# diplexer-GPS-RF360-B8666.net
KiCad netlist of a schematic drawn in EAGLE
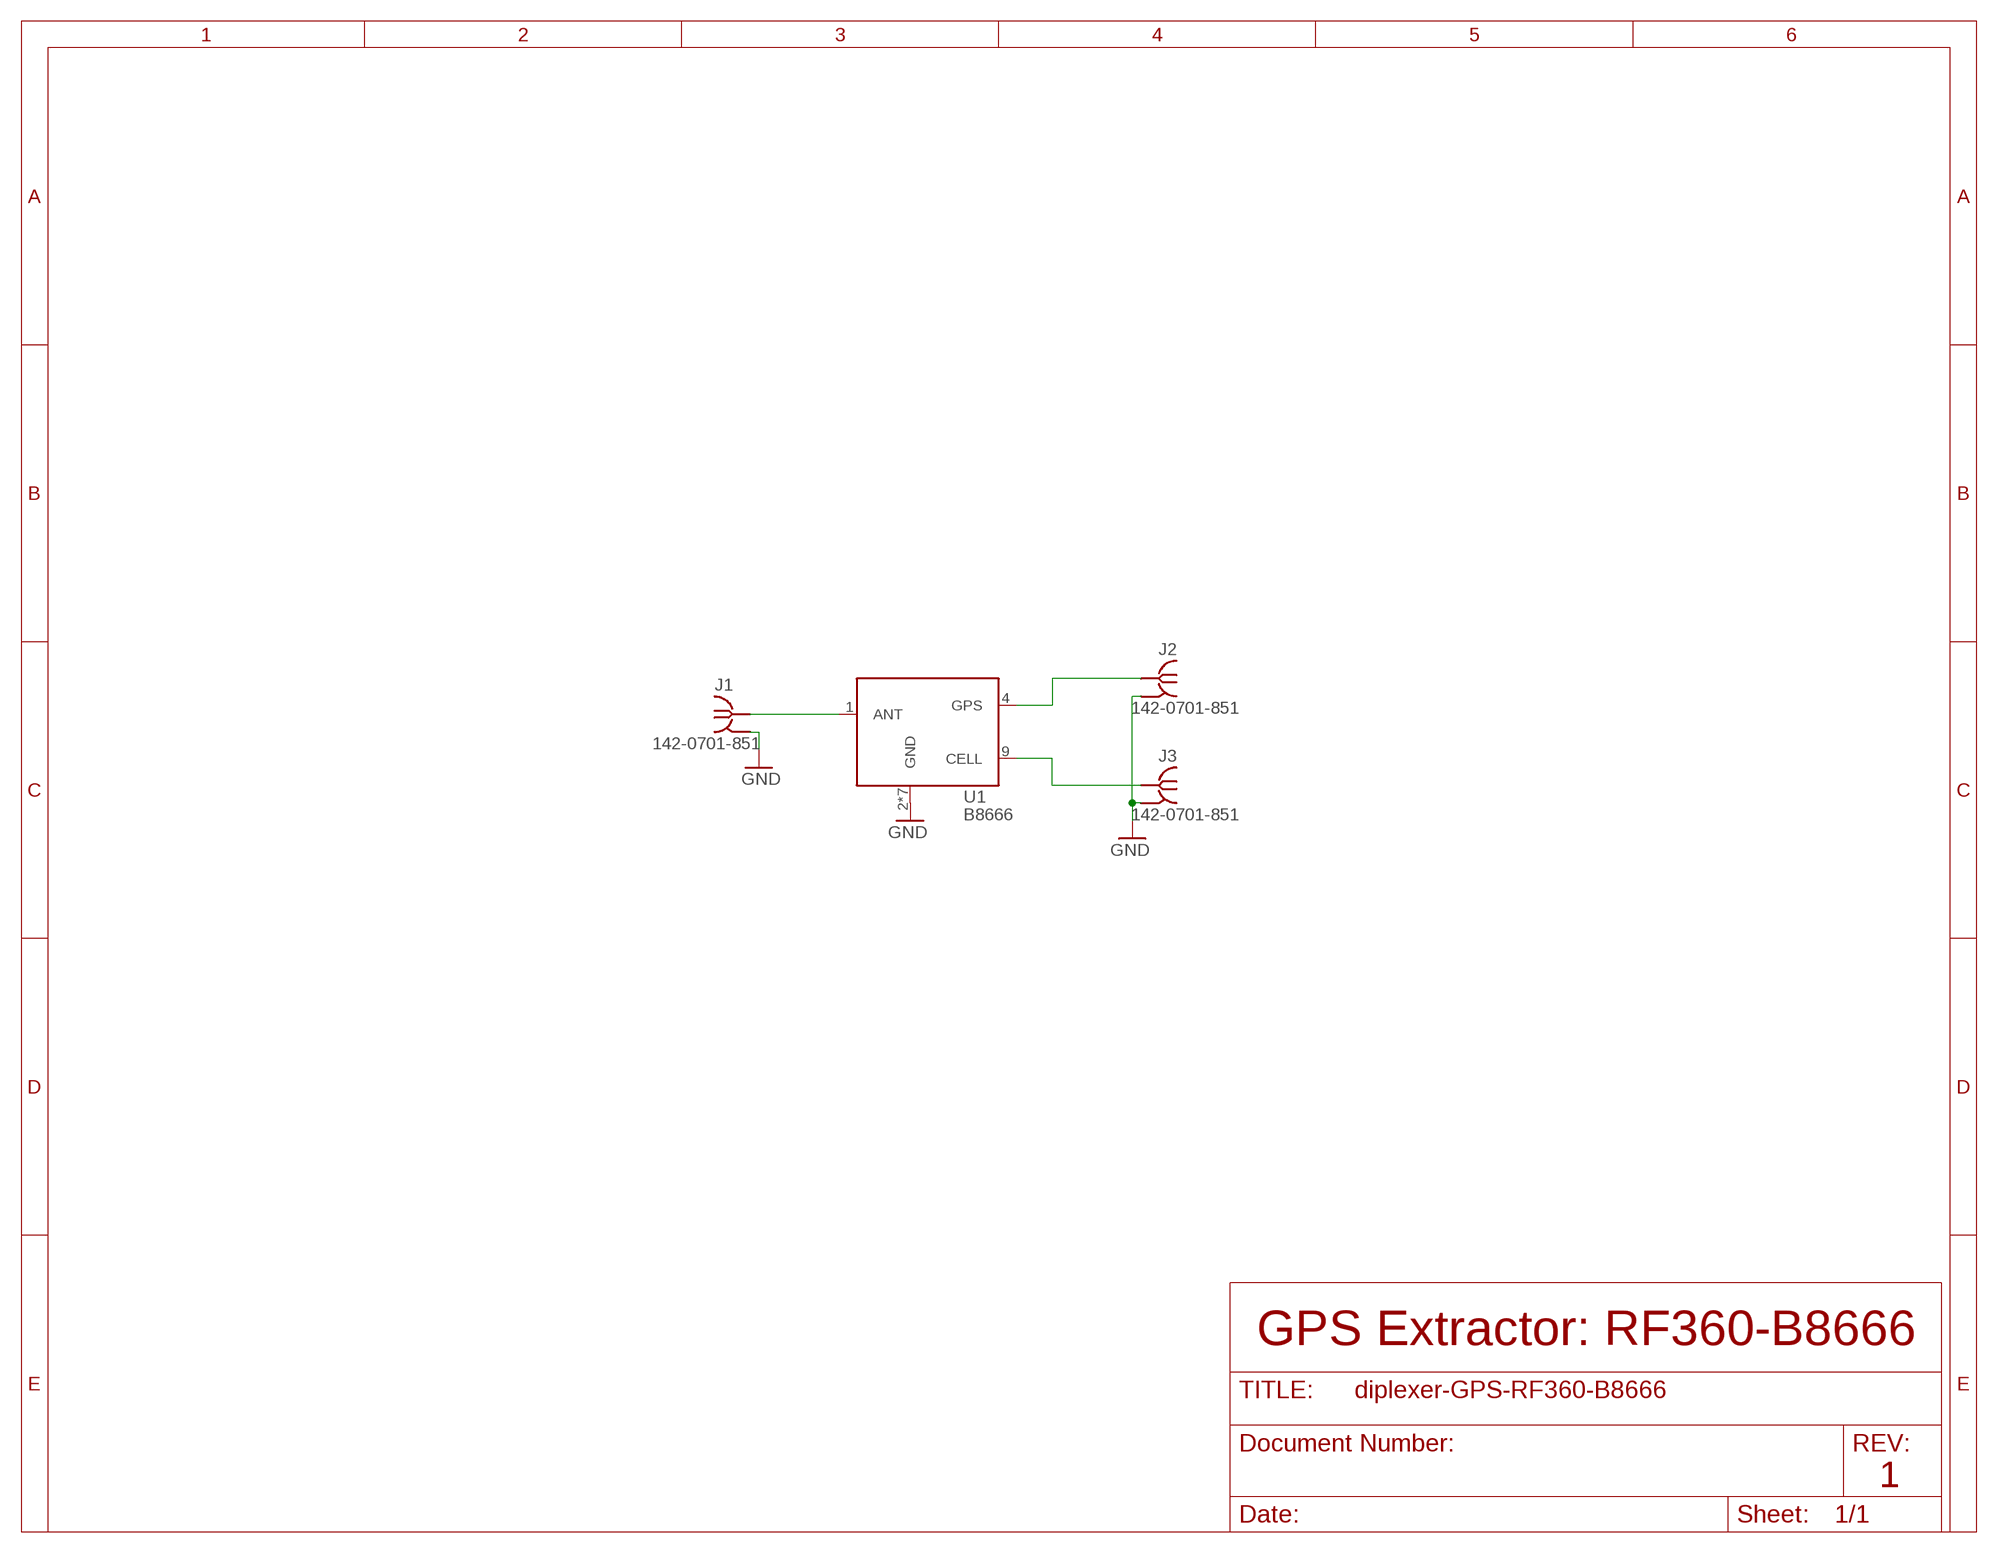
[diagram p0: schematic, sheet 1]

(export (version "E")
  (design (tool "Eeschema 10.0.6"))
  (components
    (comp (ref "J1")
      (value "142-0701-851")
      (footprint "eagle-import:142-0701-851")
      (libsource (lib "eagle-import") (part "142-0701-851"))
    )
    (comp (ref "J2")
      (value "142-0701-851")
      (footprint "eagle-import:142-0701-851")
      (libsource (lib "eagle-import") (part "142-0701-851"))
    )
    (comp (ref "J3")
      (value "142-0701-851")
      (footprint "eagle-import:142-0701-851")
      (libsource (lib "eagle-import") (part "142-0701-851"))
    )
    (comp (ref "U1")
      (value "B8666")
      (footprint "eagle-import:1.7X1.3")
      (libsource (lib "eagle-import") (part "B8666"))
    )
  )
  (nets
    (net (code "1") (name "GND") (class "Default")
      (node (ref "J1") (pin "GND1") (pinfunction "GND_GND1") (pintype "bidirectional"))
      (node (ref "J1") (pin "GND2") (pinfunction "GND_GND2") (pintype "bidirectional"))
      (node (ref "J1") (pin "GND3") (pinfunction "GND_GND3") (pintype "bidirectional"))
      (node (ref "J1") (pin "GND4") (pinfunction "GND_GND4") (pintype "bidirectional"))
      (node (ref "J2") (pin "GND1") (pinfunction "GND_GND1") (pintype "bidirectional"))
      (node (ref "J2") (pin "GND2") (pinfunction "GND_GND2") (pintype "bidirectional"))
      (node (ref "J2") (pin "GND3") (pinfunction "GND_GND3") (pintype "bidirectional"))
      (node (ref "J2") (pin "GND4") (pinfunction "GND_GND4") (pintype "bidirectional"))
      (node (ref "J3") (pin "GND1") (pinfunction "GND_GND1") (pintype "bidirectional"))
      (node (ref "J3") (pin "GND2") (pinfunction "GND_GND2") (pintype "bidirectional"))
      (node (ref "J3") (pin "GND3") (pinfunction "GND_GND3") (pintype "bidirectional"))
      (node (ref "J3") (pin "GND4") (pinfunction "GND_GND4") (pintype "bidirectional"))
      (node (ref "U1") (pin "10") (pinfunction "GND_10") (pintype "power_in"))
      (node (ref "U1") (pin "2") (pinfunction "GND_2") (pintype "power_in"))
      (node (ref "U1") (pin "3") (pinfunction "GND_3") (pintype "power_in"))
      (node (ref "U1") (pin "5") (pinfunction "GND_5") (pintype "power_in"))
      (node (ref "U1") (pin "6") (pinfunction "GND_6") (pintype "power_in"))
      (node (ref "U1") (pin "7") (pinfunction "GND_7") (pintype "power_in"))
      (node (ref "U1") (pin "8") (pinfunction "GND_8") (pintype "power_in"))
    )
    (net (code "2") (name "Net-(J1-RF)") (class "Default")
      (node (ref "J1") (pin "RF1") (pinfunction "RF_RF1") (pintype "bidirectional"))
      (node (ref "U1") (pin "1") (pinfunction "ANT_1") (pintype "input"))
    )
    (net (code "3") (name "Net-(J2-RF)") (class "Default")
      (node (ref "J2") (pin "RF1") (pinfunction "RF_RF1") (pintype "bidirectional"))
      (node (ref "U1") (pin "4") (pinfunction "GPS_4") (pintype "output"))
    )
    (net (code "4") (name "Net-(J3-RF)") (class "Default")
      (node (ref "J3") (pin "RF1") (pinfunction "RF_RF1") (pintype "bidirectional"))
      (node (ref "U1") (pin "9") (pinfunction "CELL_9") (pintype "output"))
    )
  )
)
